# cpu_board_2.net
KiCad netlist of a schematic drawn in Altium Designer
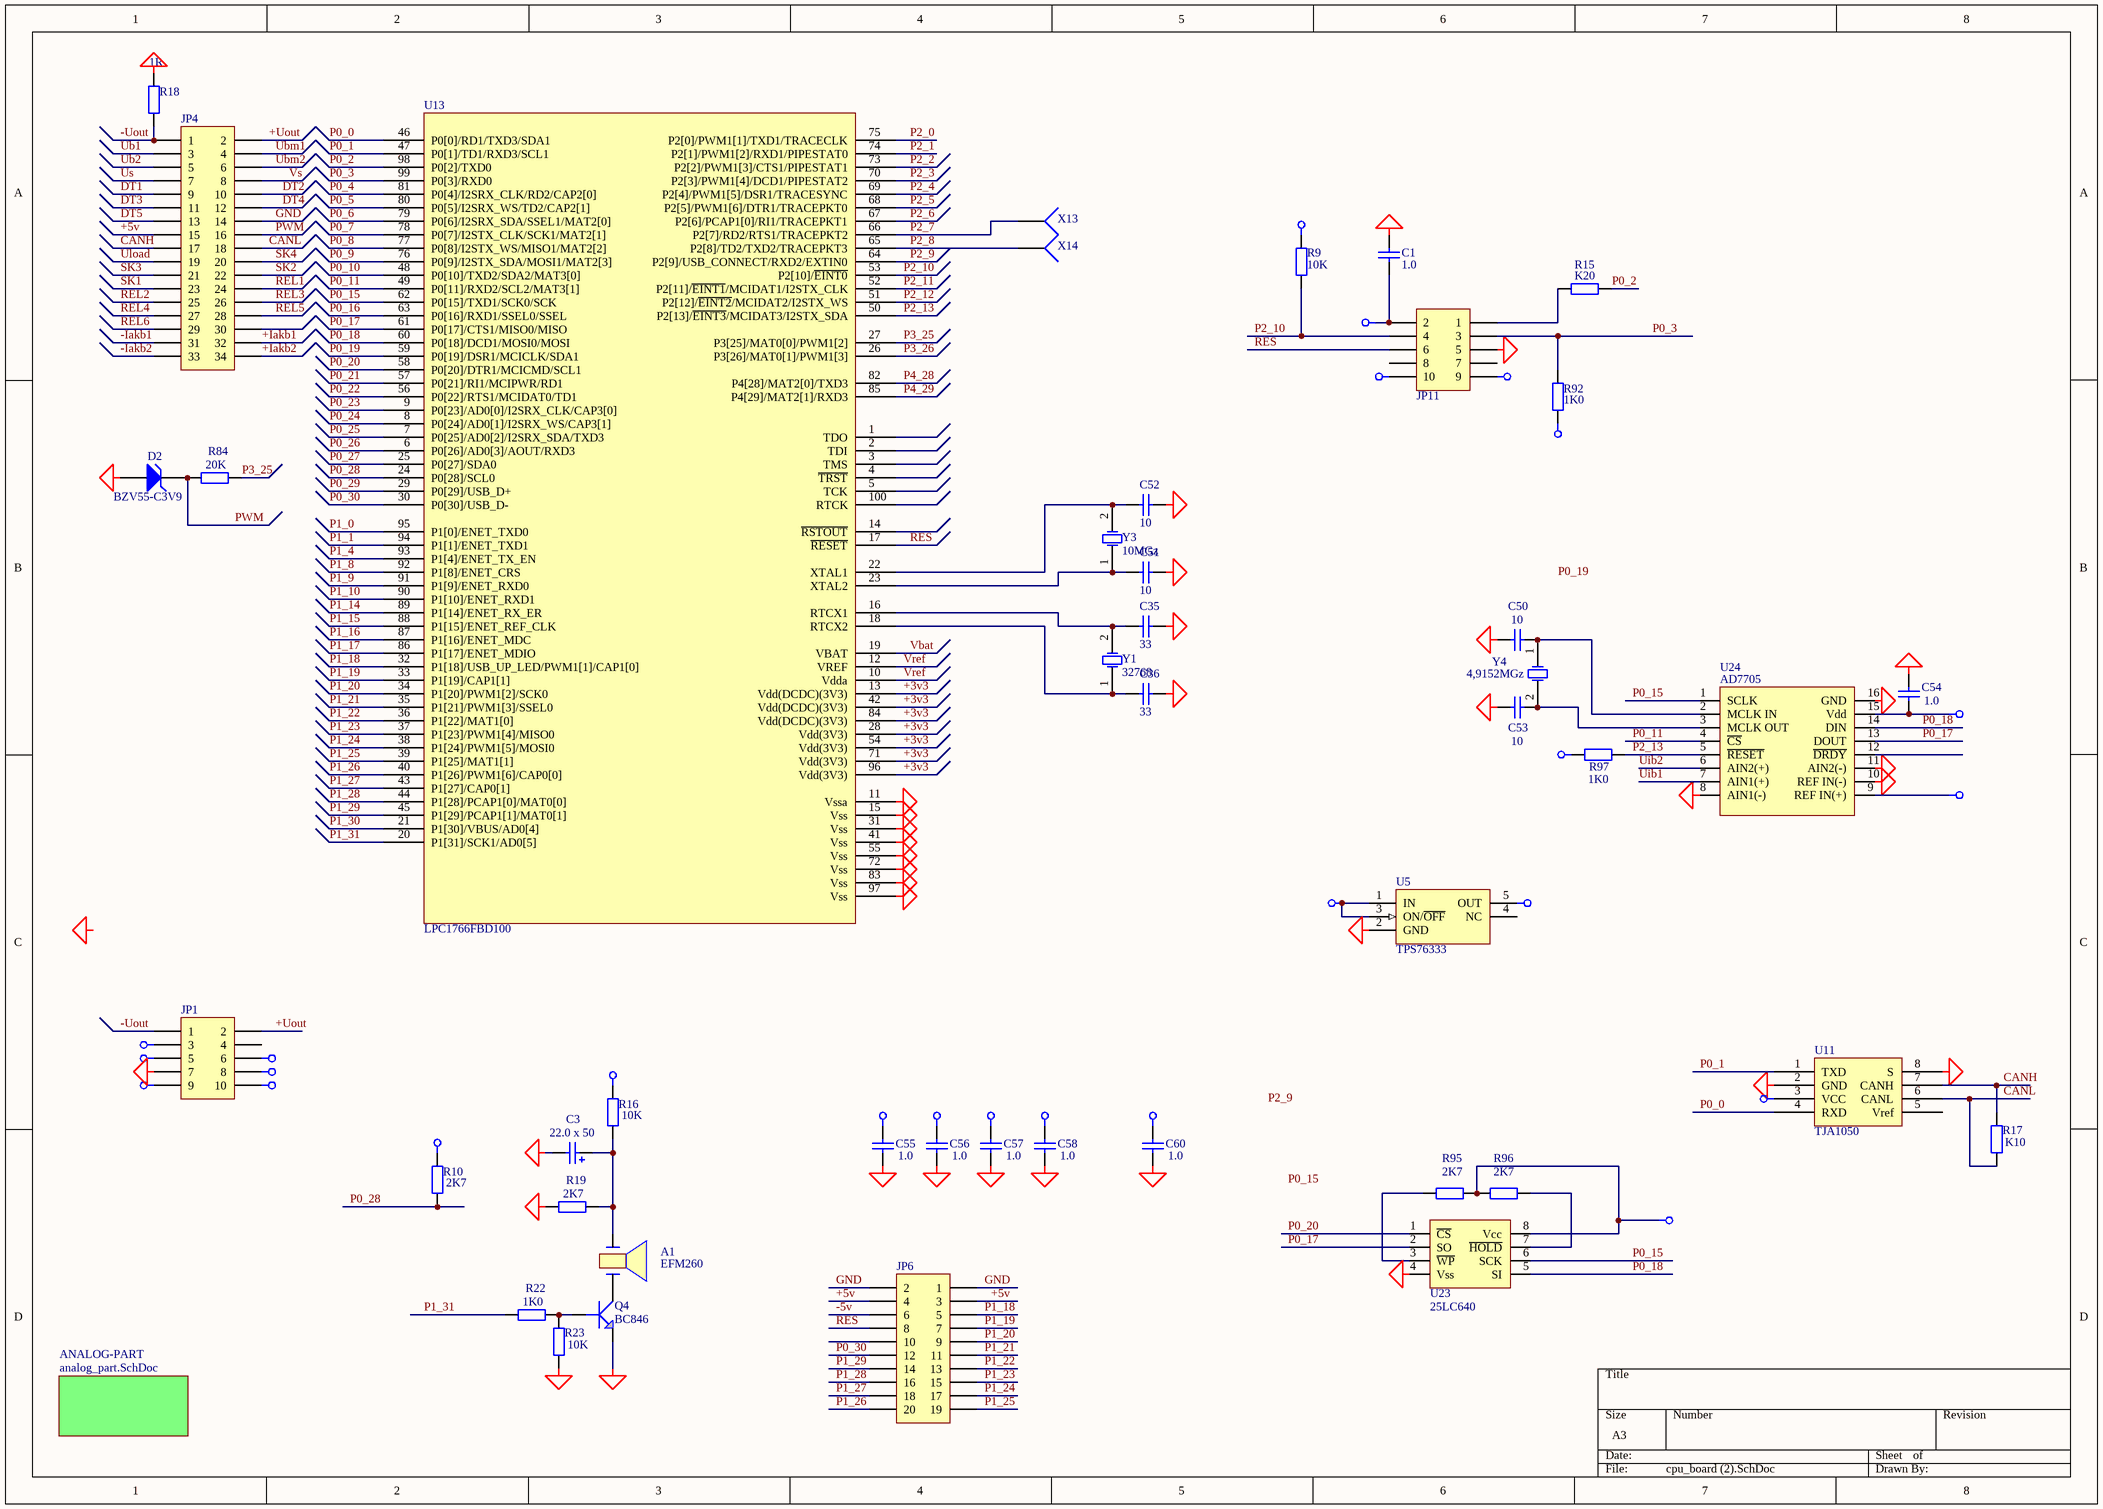
[diagram p0: cpu_board (2).SchDoc]

(export (version "E")
  (design (tool "Eeschema 10.0.6"))
  (components
    (comp (ref "A1")
      (value "EFM260")
      (footprint "Pjezo15")
      (description "Beeper")
      (libsource (lib "PAL") (part "PJEZ0"))
    )
    (comp (ref "C1")
      (value "1.0")
      (footprint "_1206")
      (description "Capacitor")
      (fields (field (name "MANUFACTURER") "Generic Components") (field (name "PUBLISHER") "Altium Limited"))
      (libsource (lib "Miscellaneous Devices") (part "Cap Semi"))
    )
    (comp (ref "C3")
      (value "22.0 x 50")
      (footprint "el3")
      (description "Polarized Capacitor (Radial)")
      (fields (field (name "MANUFACTURER") "Generic Components") (field (name "PUBLISHER") "Altium Limited"))
      (libsource (lib "PAL") (part "Cap Pol1"))
    )
    (comp (ref "C35")
      (value "33")
      (footprint "_1206")
      (description "Capacitor (Semiconductor SIM Model)")
      (fields (field (name "MANUFACTURER") "Generic Components") (field (name "PUBLISHER") "Altium Limited"))
      (libsource (lib "Miscellaneous Devices") (part "Cap Semi"))
    )
    (comp (ref "C36")
      (value "33")
      (footprint "_1206")
      (description "Capacitor (Semiconductor SIM Model)")
      (fields (field (name "MANUFACTURER") "Generic Components") (field (name "PUBLISHER") "Altium Limited"))
      (libsource (lib "Miscellaneous Devices") (part "Cap Semi"))
    )
    (comp (ref "C50")
      (value "10")
      (footprint "_1206")
      (description "Capacitor")
      (fields (field (name "MANUFACTURER") "Generic Components") (field (name "PUBLISHER") "Altium Limited"))
      (libsource (lib "") (part "Cap Semi_1"))
    )
    (comp (ref "C51")
      (value "10")
      (footprint "_1206")
      (description "Capacitor")
      (fields (field (name "MANUFACTURER") "Generic Components") (field (name "PUBLISHER") "Altium Limited"))
      (libsource (lib "Miscellaneous Devices") (part "Cap Semi"))
    )
    (comp (ref "C52")
      (value "10")
      (footprint "_1206")
      (description "Capacitor")
      (fields (field (name "MANUFACTURER") "Generic Components") (field (name "PUBLISHER") "Altium Limited"))
      (libsource (lib "Miscellaneous Devices") (part "Cap Semi"))
    )
    (comp (ref "C53")
      (value "10")
      (footprint "_1206")
      (description "Capacitor")
      (fields (field (name "MANUFACTURER") "Generic Components") (field (name "PUBLISHER") "Altium Limited"))
      (libsource (lib "") (part "Cap Semi_1"))
    )
    (comp (ref "C54")
      (value "1.0")
      (footprint "_1206")
      (description "Capacitor")
      (fields (field (name "MANUFACTURER") "Generic Components") (field (name "PUBLISHER") "Altium Limited"))
      (libsource (lib "Miscellaneous Devices") (part "Cap Semi"))
    )
    (comp (ref "C55")
      (value "1.0")
      (footprint "_1206")
      (description "Capacitor")
      (fields (field (name "MANUFACTURER") "Generic Components") (field (name "PUBLISHER") "Altium Limited"))
      (libsource (lib "Miscellaneous Devices") (part "Cap Semi"))
    )
    (comp (ref "C56")
      (value "1.0")
      (footprint "_1206")
      (description "Capacitor")
      (fields (field (name "MANUFACTURER") "Generic Components") (field (name "PUBLISHER") "Altium Limited"))
      (libsource (lib "Miscellaneous Devices") (part "Cap Semi"))
    )
    (comp (ref "C57")
      (value "1.0")
      (footprint "_1206")
      (description "Capacitor")
      (fields (field (name "MANUFACTURER") "Generic Components") (field (name "PUBLISHER") "Altium Limited"))
      (libsource (lib "Miscellaneous Devices") (part "Cap Semi"))
    )
    (comp (ref "C58")
      (value "1.0")
      (footprint "_1206")
      (description "Capacitor")
      (fields (field (name "MANUFACTURER") "Generic Components") (field (name "PUBLISHER") "Altium Limited"))
      (libsource (lib "Miscellaneous Devices") (part "Cap Semi"))
    )
    (comp (ref "C60")
      (value "1.0")
      (footprint "_1206")
      (description "Capacitor")
      (fields (field (name "MANUFACTURER") "Generic Components") (field (name "PUBLISHER") "Altium Limited"))
      (libsource (lib "Miscellaneous Devices") (part "Cap Semi"))
    )
    (comp (ref "D2")
      (value "BZV55-C3V9")
      (footprint "_1206d")
      (description "Zener Diode")
      (fields (field (name "MANUFACTURER") "Generic Components") (field (name "PUBLISHER") "Altium Limited"))
      (libsource (lib "Miscellaneous Devices") (part "D Zener"))
    )
    (comp (ref "JP1")
      (value "PBD-10")
      (footprint "HDR2X5")
      (description "Header, 5-Pin, Dual row")
      (fields (field (name "MANUFACTURER") "Generic Components") (field (name "PUBLISHER") "Altium Limited"))
      (libsource (lib "Miscellaneous Connectors") (part "Header 5X2"))
    )
    (comp (ref "JP4")
      (value "IDC34")
      (footprint "IDC34M")
      (description "Header, 17-Pin, Dual row")
      (fields (field (name "MANUFACTURER") "Generic Components") (field (name "PUBLISHER") "Altium Limited"))
      (libsource (lib "Miscellaneous Connectors") (part "Header 17X2"))
    )
    (comp (ref "JP6")
      (value "PBD-20")
      (footprint "HDR2X10")
      (description "Header, 10-Pin, Dual row")
      (fields (field (name "MANUFACTURER") "Generic Components") (field (name "PUBLISHER") "Altium Limited"))
      (libsource (lib "Miscellaneous Connectors") (part "Header 10X2"))
    )
    (comp (ref "JP11")
      (value "PLHD-10")
      (footprint "HDR2X5")
      (description "Header, 5-Pin, Dual row")
      (fields (field (name "MANUFACTURER") "Generic Components") (field (name "PUBLISHER") "Altium Limited"))
      (libsource (lib "") (part "Header 5X2_1"))
    )
    (comp (ref "Q4")
      (value "BC846")
      (footprint "SO-G3")
      (description "Bipolar transistor")
      (libsource (lib "MAIN") (part "GT122"))
    )
    (comp (ref "R9")
      (value "10K")
      (footprint "_1206")
      (description "Resistor")
      (fields (field (name "MANUFACTURER") "Generic Components") (field (name "PUBLISHER") "Altium Limited"))
      (libsource (lib "") (part "Res2_3"))
    )
    (comp (ref "R10")
      (value "2K7")
      (footprint "_1206")
      (description "Resistor")
      (fields (field (name "MANUFACTURER") "Generic Components") (field (name "PUBLISHER") "Altium Limited"))
      (libsource (lib "Miscellaneous Devices") (part "Res2"))
    )
    (comp (ref "R15")
      (value "K20")
      (footprint "_1206")
      (description "Resistor")
      (fields (field (name "MANUFACTURER") "Generic Components") (field (name "PUBLISHER") "Altium Limited"))
      (libsource (lib "") (part "Res2_2"))
    )
    (comp (ref "R16")
      (value "10K")
      (footprint "_1206")
      (description "Resistor")
      (fields (field (name "MANUFACTURER") "Generic Components") (field (name "PUBLISHER") "Altium Limited"))
      (libsource (lib "Miscellaneous Devices") (part "Res2"))
    )
    (comp (ref "R17")
      (value "K10")
      (footprint "_1206")
      (description "Resistor")
      (fields (field (name "MANUFACTURER") "Generic Components") (field (name "PUBLISHER") "Altium Limited"))
      (libsource (lib "Miscellaneous Devices") (part "Res2"))
    )
    (comp (ref "R18")
      (value "1R")
      (footprint "_1206")
      (description "Resistor")
      (fields (field (name "MANUFACTURER") "Generic Components") (field (name "PUBLISHER") "Altium Limited"))
      (libsource (lib "Miscellaneous Devices") (part "Res2"))
    )
    (comp (ref "R19")
      (value "2K7")
      (footprint "_1206")
      (description "Resistor")
      (fields (field (name "MANUFACTURER") "Generic Components") (field (name "PUBLISHER") "Altium Limited"))
      (libsource (lib "") (part "Res2_2"))
    )
    (comp (ref "R22")
      (value "1K0")
      (footprint "_1206")
      (description "Resistor")
      (fields (field (name "MANUFACTURER") "Generic Components") (field (name "PUBLISHER") "Altium Limited"))
      (libsource (lib "") (part "Res2_2"))
    )
    (comp (ref "R23")
      (value "10K")
      (footprint "_1206")
      (description "Resistor")
      (fields (field (name "MANUFACTURER") "Generic Components") (field (name "PUBLISHER") "Altium Limited"))
      (libsource (lib "Miscellaneous Devices") (part "Res2"))
    )
    (comp (ref "R84")
      (value "20K")
      (footprint "_1206")
      (description "Resistor")
      (fields (field (name "MANUFACTURER") "Generic Components") (field (name "PUBLISHER") "Altium Limited"))
      (libsource (lib "") (part "Res2_2"))
    )
    (comp (ref "R92")
      (value "1K0")
      (footprint "_1206")
      (description "Resistor")
      (fields (field (name "MANUFACTURER") "Generic Components") (field (name "PUBLISHER") "Altium Limited"))
      (libsource (lib "") (part "Res2_1"))
    )
    (comp (ref "R95")
      (value "2K7")
      (footprint "_1206")
      (description "Resistor")
      (fields (field (name "MANUFACTURER") "Generic Components") (field (name "PUBLISHER") "Altium Limited"))
      (libsource (lib "") (part "Res2_2"))
    )
    (comp (ref "R96")
      (value "2K7")
      (footprint "_1206")
      (description "Resistor")
      (fields (field (name "MANUFACTURER") "Generic Components") (field (name "PUBLISHER") "Altium Limited"))
      (libsource (lib "") (part "Res2_2"))
    )
    (comp (ref "R97")
      (value "1K0")
      (footprint "_1206")
      (description "Resistor")
      (fields (field (name "MANUFACTURER") "Generic Components") (field (name "PUBLISHER") "Altium Limited"))
      (libsource (lib "") (part "Res2_1"))
    )
    (comp (ref "U5")
      (value "TPS76333")
      (footprint "SO-G5/P.95")
      (description "Voltage Regulator")
      (fields
        (field (name "MANUFACTURER") "National Semiconductor")
        (field (name "PUBLISHER") "Altium Limited")
      )
      (libsource (lib "NSC Power Mgt Voltage Regulator") (part "LP2980AIM5-3.3"))
    )
    (comp (ref "U11") (value "TJA1050") (footprint "SO-G8/D5") (libsource (lib "PAL") (part "TJA1050")))
    (comp (ref "U13")
      (value "LPC1766FBD100")
      (footprint "LPC2368")
      (libsource (lib "PAL") (part "LPC2368FBD100"))
    )
    (comp (ref "U23")
      (value "25LC640")
      (footprint "SO-G8/D5")
      (description "Memory")
      (libsource (lib "PAL") (part "25LC640"))
    )
    (comp (ref "U24")
      (value "AD7705")
      (footprint "SO-G16/D10.4")
      (description "ADC")
      (libsource (lib "PAL") (part "AD7705"))
    )
    (comp (ref "X13")
      (value "~")
      (footprint "PIN1")
      (description "Socket")
      (fields (field (name "MANUFACTURER") "Generic Components") (field (name "PUBLISHER") "Altium Limited"))
      (libsource (lib "Miscellaneous Connectors") (part "Socket"))
    )
    (comp (ref "X14")
      (value "~")
      (footprint "PIN1")
      (description "Socket")
      (fields (field (name "MANUFACTURER") "Generic Components") (field (name "PUBLISHER") "Altium Limited"))
      (libsource (lib "Miscellaneous Connectors") (part "Socket"))
    )
    (comp (ref "Y1")
      (value "32768")
      (footprint "QWARZ2")
      (description "Crystal Oscillator")
      (fields (field (name "MANUFACTURER") "Generic Components") (field (name "PUBLISHER") "Altium Limited"))
      (libsource (lib "") (part "XTAL_1"))
    )
    (comp (ref "Y3")
      (value "10MGz")
      (footprint "QWARZ1")
      (description "Crystal Oscillator")
      (fields (field (name "MANUFACTURER") "Generic Components") (field (name "PUBLISHER") "Altium Limited"))
      (libsource (lib "") (part "XTAL_1"))
    )
    (comp (ref "Y4")
      (value "4,9152MGz")
      (footprint "QWARZ1")
      (description "Crystal Oscillator")
      (fields (field (name "MANUFACTURER") "Generic Components") (field (name "PUBLISHER") "Altium Limited"))
      (libsource (lib "Miscellaneous Devices") (part "XTAL"))
    )
  )
  (nets
    (net (code "1") (name "+3v3") (class "Default")
      (node (ref "C1") (pin "1") (pinfunction "1_1") (pintype "passive"))
      (node (ref "C58") (pin "2") (pinfunction "2_2") (pintype "passive"))
      (node (ref "JP1") (pin "3") (pinfunction "3_3") (pintype "passive"))
      (node (ref "JP11") (pin "2") (pinfunction "2_2") (pintype "passive"))
      (node (ref "R10") (pin "2") (pinfunction "2_2") (pintype "passive"))
      (node (ref "R9") (pin "1") (pinfunction "1_1") (pintype "passive"))
      (node (ref "R92") (pin "2") (pinfunction "2_2") (pintype "passive"))
      (node (ref "U13") (pin "13") (pinfunction "Vdd(DCDC)(3V3)_13") (pintype "passive"))
      (node (ref "U13") (pin "28") (pinfunction "Vdd(3V3)_28") (pintype "passive"))
      (node (ref "U13") (pin "42") (pinfunction "Vdd(DCDC)(3V3)_42") (pintype "passive"))
      (node (ref "U13") (pin "54") (pinfunction "Vdd(3V3)_54") (pintype "passive"))
      (node (ref "U13") (pin "71") (pinfunction "Vdd(3V3)_71") (pintype "passive"))
      (node (ref "U13") (pin "84") (pinfunction "Vdd(DCDC)(3V3)_84") (pintype "passive"))
      (node (ref "U13") (pin "96") (pinfunction "Vdd(3V3)_96") (pintype "passive"))
    )
    (net (code "2") (name "+5v") (class "Default")
      (node (ref "C54") (pin "2") (pinfunction "2_2") (pintype "passive"))
      (node (ref "C55") (pin "2") (pinfunction "2_2") (pintype "passive"))
      (node (ref "C57") (pin "2") (pinfunction "2_2") (pintype "passive"))
      (node (ref "C60") (pin "2") (pinfunction "2_2") (pintype "passive"))
      (node (ref "JP1") (pin "5") (pinfunction "5_5") (pintype "passive"))
      (node (ref "JP4") (pin "15") (pinfunction "15_15") (pintype "passive"))
      (node (ref "JP6") (pin "3") (pinfunction "3_3") (pintype "passive"))
      (node (ref "JP6") (pin "4") (pinfunction "4_4") (pintype "passive"))
      (node (ref "R95") (pin "2") (pinfunction "2_2") (pintype "passive"))
      (node (ref "R96") (pin "1") (pinfunction "1_1") (pintype "passive"))
      (node (ref "R97") (pin "2") (pinfunction "2_2") (pintype "passive"))
      (node (ref "U11") (pin "3") (pinfunction "VCC_3") (pintype "passive"))
      (node (ref "U23") (pin "8") (pinfunction "Vcc_8") (pintype "passive"))
      (node (ref "U24") (pin "15") (pinfunction "Vdd_15") (pintype "passive"))
      (node (ref "U5") (pin "1") (pinfunction "IN_1") (pintype "power_in"))
      (node (ref "U5") (pin "3") (pinfunction "ON/~{OFF}_3") (pintype "input"))
    )
    (net (code "3") (name "+5v_iz") (class "Default")
      (node (ref "JP1") (pin "10") (pinfunction "10_10") (pintype "passive"))
      (node (ref "JP11") (pin "9") (pinfunction "9_9") (pintype "passive"))
    )
    (net (code "4") (name "+Uout") (class "Default")
      (node (ref "JP1") (pin "2") (pinfunction "2_2") (pintype "passive"))
      (node (ref "JP4") (pin "2") (pinfunction "2_2") (pintype "passive"))
      (node (ref "R16") (pin "2") (pinfunction "2_2") (pintype "passive"))
    )
    (net (code "5") (name "-5v") (class "Default")
      (node (ref "C56") (pin "2") (pinfunction "2_2") (pintype "passive"))
      (node (ref "JP1") (pin "8") (pinfunction "8_8") (pintype "passive"))
      (node (ref "JP6") (pin "6") (pinfunction "6_6") (pintype "passive"))
    )
    (net (code "6") (name "-5v_iz") (class "Default")
      (node (ref "JP1") (pin "9") (pinfunction "9_9") (pintype "passive"))
      (node (ref "JP11") (pin "10") (pinfunction "10_10") (pintype "passive"))
    )
    (net (code "7") (name "/+Iakb1") (class "Default")
      (node (ref "JP4") (pin "32") (pinfunction "32_32") (pintype "passive"))
    )
    (net (code "8") (name "/+Iakb2") (class "Default")
      (node (ref "JP4") (pin "34") (pinfunction "34_34") (pintype "passive"))
    )
    (net (code "9") (name "/-Iakb1") (class "Default")
      (node (ref "JP4") (pin "31") (pinfunction "31_31") (pintype "passive"))
    )
    (net (code "10") (name "/-Iakb2") (class "Default")
      (node (ref "JP4") (pin "33") (pinfunction "33_33") (pintype "passive"))
    )
    (net (code "11") (name "/-Uout") (class "Default")
      (node (ref "JP1") (pin "1") (pinfunction "1_1") (pintype "passive"))
      (node (ref "JP4") (pin "1") (pinfunction "1_1") (pintype "passive"))
      (node (ref "R18") (pin "1") (pinfunction "1_1") (pintype "passive"))
    )
    (net (code "12") (name "/CANH") (class "Default")
      (node (ref "JP4") (pin "17") (pinfunction "17_17") (pintype "passive"))
      (node (ref "R17") (pin "2") (pinfunction "2_2") (pintype "passive"))
      (node (ref "U11") (pin "7") (pinfunction "CANH_7") (pintype "passive"))
    )
    (net (code "13") (name "/CANL") (class "Default")
      (node (ref "JP4") (pin "18") (pinfunction "18_18") (pintype "passive"))
      (node (ref "R17") (pin "1") (pinfunction "1_1") (pintype "passive"))
      (node (ref "U11") (pin "6") (pinfunction "CANL_6") (pintype "passive"))
    )
    (net (code "14") (name "/DT1") (class "Default")
      (node (ref "JP4") (pin "9") (pinfunction "9_9") (pintype "passive"))
    )
    (net (code "15") (name "/DT2") (class "Default")
      (node (ref "JP4") (pin "10") (pinfunction "10_10") (pintype "passive"))
    )
    (net (code "16") (name "/DT3") (class "Default")
      (node (ref "JP4") (pin "11") (pinfunction "11_11") (pintype "passive"))
    )
    (net (code "17") (name "/DT4") (class "Default")
      (node (ref "JP4") (pin "12") (pinfunction "12_12") (pintype "passive"))
    )
    (net (code "18") (name "/DT5") (class "Default")
      (node (ref "JP4") (pin "13") (pinfunction "13_13") (pintype "passive"))
    )
    (net (code "19") (name "/P0_0") (class "Default")
      (node (ref "U11") (pin "4") (pinfunction "RXD_4") (pintype "passive"))
      (node (ref "U13") (pin "46") (pinfunction "P0[0]/RD1/TXD3/SDA1_46") (pintype "passive"))
    )
    (net (code "20") (name "/P0_1") (class "Default")
      (node (ref "U11") (pin "1") (pinfunction "TXD_1") (pintype "passive"))
      (node (ref "U13") (pin "47") (pinfunction "P0[1]/TD1/RXD3/SCL1_47") (pintype "passive"))
    )
    (net (code "21") (name "/P0_2") (class "Default")
      (node (ref "R15") (pin "2") (pinfunction "2_2") (pintype "passive"))
      (node (ref "U13") (pin "98") (pinfunction "P0[2]/TXD0_98") (pintype "passive"))
    )
    (net (code "22") (name "/P0_3") (class "Default")
      (node (ref "JP11") (pin "3") (pinfunction "3_3") (pintype "passive"))
      (node (ref "R92") (pin "1") (pinfunction "1_1") (pintype "passive"))
      (node (ref "U13") (pin "99") (pinfunction "P0[3]/RXD0_99") (pintype "passive"))
    )
    (net (code "23") (name "/P0_4") (class "Default")
      (node (ref "U13") (pin "81") (pinfunction "P0[4]/I2SRX_CLK/RD2/CAP2[0]_81") (pintype "passive"))
    )
    (net (code "24") (name "/P0_5") (class "Default")
      (node (ref "U13") (pin "80") (pinfunction "P0[5]/I2SRX_WS/TD2/CAP2[1]_80") (pintype "passive"))
    )
    (net (code "25") (name "/P0_6") (class "Default")
      (node (ref "U13") (pin "79") (pinfunction "P0[6]/I2SRX_SDA/SSEL1/MAT2[0]_79") (pintype "passive"))
    )
    (net (code "26") (name "/P0_7") (class "Default")
      (node (ref "U13") (pin "78") (pinfunction "P0[7]/I2STX_CLK/SCK1/MAT2[1]_78") (pintype "passive"))
    )
    (net (code "27") (name "/P0_8") (class "Default")
      (node (ref "U13") (pin "77") (pinfunction "P0[8]/I2STX_WS/MISO1/MAT2[2]_77") (pintype "passive"))
    )
    (net (code "28") (name "/P0_9") (class "Default")
      (node (ref "U13") (pin "76") (pinfunction "P0[9]/I2STX_SDA/MOSI1/MAT2[3]_76") (pintype "passive"))
    )
    (net (code "29") (name "/P0_10") (class "Default")
      (node (ref "U13") (pin "48") (pinfunction "P0[10]/TXD2/SDA2/MAT3[0]_48") (pintype "passive"))
    )
    (net (code "30") (name "/P0_11") (class "Default")
      (node (ref "U13") (pin "49") (pinfunction "P0[11]/RXD2/SCL2/MAT3[1]_49") (pintype "passive"))
      (node (ref "U24") (pin "4") (pinfunction "~{CS}_4") (pintype "passive"))
    )
    (net (code "31") (name "/P0_15") (class "Default")
      (node (ref "U13") (pin "62") (pinfunction "P0[15]/TXD1/SCK0/SCK_62") (pintype "passive"))
      (node (ref "U23") (pin "6") (pinfunction "SCK_6") (pintype "passive"))
      (node (ref "U24") (pin "1") (pinfunction "SCLK_1") (pintype "passive"))
    )
    (net (code "32") (name "/P0_16") (class "Default")
      (node (ref "U13") (pin "63") (pinfunction "P0[16]/RXD1/SSEL0/SSEL_63") (pintype "passive"))
    )
    (net (code "33") (name "/P0_17") (class "Default")
      (node (ref "U13") (pin "61") (pinfunction "P0[17]/CTS1/MISO0/MISO_61") (pintype "passive"))
      (node (ref "U23") (pin "2") (pinfunction "SO_2") (pintype "passive"))
      (node (ref "U24") (pin "13") (pinfunction "DOUT_13") (pintype "passive"))
    )
    (net (code "34") (name "/P0_18") (class "Default")
      (node (ref "U13") (pin "60") (pinfunction "P0[18]/DCD1/MOSI0/MOSI_60") (pintype "passive"))
      (node (ref "U23") (pin "5") (pinfunction "SI_5") (pintype "passive"))
      (node (ref "U24") (pin "14") (pinfunction "DIN_14") (pintype "passive"))
    )
    (net (code "35") (name "/P0_19") (class "Default")
      (node (ref "U13") (pin "59") (pinfunction "P0[19]/DSR1/MCICLK/SDA1_59") (pintype "passive"))
    )
    (net (code "36") (name "/P0_20") (class "Default")
      (node (ref "U13") (pin "58") (pinfunction "P0[20]/DTR1/MCICMD/SCL1_58") (pintype "passive"))
      (node (ref "U23") (pin "1") (pinfunction "~{CS}_1") (pintype "passive"))
    )
    (net (code "37") (name "/P0_21") (class "Default")
      (node (ref "U13") (pin "57") (pinfunction "P0[21]/RI1/MCIPWR/RD1_57") (pintype "passive"))
    )
    (net (code "38") (name "/P0_22") (class "Default")
      (node (ref "U13") (pin "56") (pinfunction "P0[22]/RTS1/MCIDAT0/TD1_56") (pintype "passive"))
    )
    (net (code "39") (name "/P0_23") (class "Default")
      (node (ref "U13") (pin "9") (pinfunction "P0[23]/AD0[0]/I2SRX_CLK/CAP3[0]_9") (pintype "passive"))
    )
    (net (code "40") (name "/P0_24") (class "Default")
      (node (ref "U13") (pin "8") (pinfunction "P0[24]/AD0[1]/I2SRX_WS/CAP3[1]_8") (pintype "passive"))
    )
    (net (code "41") (name "/P0_25") (class "Default")
      (node (ref "U13") (pin "7") (pinfunction "P0[25]/AD0[2]/I2SRX_SDA/TXD3_7") (pintype "passive"))
    )
    (net (code "42") (name "/P0_26") (class "Default")
      (node (ref "U13") (pin "6") (pinfunction "P0[26]/AD0[3]/AOUT/RXD3_6") (pintype "passive"))
    )
    (net (code "43") (name "/P0_27") (class "Default")
      (node (ref "U13") (pin "25") (pinfunction "P0[27]/SDA0_25") (pintype "passive"))
    )
    (net (code "44") (name "/P0_28") (class "Default")
      (node (ref "R10") (pin "1") (pinfunction "1_1") (pintype "passive"))
      (node (ref "U13") (pin "24") (pinfunction "P0[28]/SCL0_24") (pintype "passive"))
    )
    (net (code "45") (name "/P0_29") (class "Default")
      (node (ref "U13") (pin "29") (pinfunction "P0[29]/USB_D+_29") (pintype "passive"))
    )
    (net (code "46") (name "/P0_30") (class "Default")
      (node (ref "JP6") (pin "12") (pinfunction "12_12") (pintype "passive"))
      (node (ref "U13") (pin "30") (pinfunction "P0[30]/USB_D-_30") (pintype "passive"))
    )
    (net (code "47") (name "/P1_0") (class "Default")
      (node (ref "U13") (pin "95") (pinfunction "P1[0]/ENET_TXD0_95") (pintype "passive"))
    )
    (net (code "48") (name "/P1_1") (class "Default")
      (node (ref "U13") (pin "94") (pinfunction "P1[1]/ENET_TXD1_94") (pintype "passive"))
    )
    (net (code "49") (name "/P1_4") (class "Default")
      (node (ref "U13") (pin "93") (pinfunction "P1[4]/ENET_TX_EN_93") (pintype "passive"))
    )
    (net (code "50") (name "/P1_8") (class "Default")
      (node (ref "U13") (pin "92") (pinfunction "P1[8]/ENET_CRS_92") (pintype "passive"))
    )
    (net (code "51") (name "/P1_9") (class "Default")
      (node (ref "U13") (pin "91") (pinfunction "P1[9]/ENET_RXD0_91") (pintype "passive"))
    )
    (net (code "52") (name "/P1_10") (class "Default")
      (node (ref "U13") (pin "90") (pinfunction "P1[10]/ENET_RXD1_90") (pintype "passive"))
    )
    (net (code "53") (name "/P1_14") (class "Default")
      (node (ref "U13") (pin "89") (pinfunction "P1[14]/ENET_RX_ER_89") (pintype "passive"))
    )
    (net (code "54") (name "/P1_15") (class "Default")
      (node (ref "U13") (pin "88") (pinfunction "P1[15]/ENET_REF_CLK_88") (pintype "passive"))
    )
    (net (code "55") (name "/P1_16") (class "Default")
      (node (ref "U13") (pin "87") (pinfunction "P1[16]/ENET_MDC_87") (pintype "passive"))
    )
    (net (code "56") (name "/P1_17") (class "Default")
      (node (ref "U13") (pin "86") (pinfunction "P1[17]/ENET_MDIO_86") (pintype "passive"))
    )
    (net (code "57") (name "/P1_18") (class "Default")
      (node (ref "JP6") (pin "5") (pinfunction "5_5") (pintype "passive"))
      (node (ref "U13") (pin "32") (pinfunction "P1[18]/USB_UP_LED/PWM1[1]/CAP1[0]_32") (pintype "passive"))
    )
    (net (code "58") (name "/P1_19") (class "Default")
      (node (ref "JP6") (pin "7") (pinfunction "7_7") (pintype "passive"))
      (node (ref "U13") (pin "33") (pinfunction "P1[19]/CAP1[1]_33") (pintype "passive"))
    )
    (net (code "59") (name "/P1_20") (class "Default")
      (node (ref "JP6") (pin "9") (pinfunction "9_9") (pintype "passive"))
      (node (ref "U13") (pin "34") (pinfunction "P1[20]/PWM1[2]/SCK0_34") (pintype "passive"))
    )
    (net (code "60") (name "/P1_21") (class "Default")
      (node (ref "JP6") (pin "11") (pinfunction "11_11") (pintype "passive"))
      (node (ref "U13") (pin "35") (pinfunction "P1[21]/PWM1[3]/SSEL0_35") (pintype "passive"))
    )
    (net (code "61") (name "/P1_22") (class "Default")
      (node (ref "JP6") (pin "13") (pinfunction "13_13") (pintype "passive"))
      (node (ref "U13") (pin "36") (pinfunction "P1[22]/MAT1[0]_36") (pintype "passive"))
    )
    (net (code "62") (name "/P1_23") (class "Default")
      (node (ref "JP6") (pin "15") (pinfunction "15_15") (pintype "passive"))
      (node (ref "U13") (pin "37") (pinfunction "P1[23]/PWM1[4]/MISO0_37") (pintype "passive"))
    )
    (net (code "63") (name "/P1_24") (class "Default")
      (node (ref "JP6") (pin "17") (pinfunction "17_17") (pintype "passive"))
      (node (ref "U13") (pin "38") (pinfunction "P1[24]/PWM1[5]/MOSI0_38") (pintype "passive"))
    )
    (net (code "64") (name "/P1_25") (class "Default")
      (node (ref "JP6") (pin "19") (pinfunction "19_19") (pintype "passive"))
      (node (ref "U13") (pin "39") (pinfunction "P1[25]/MAT1[1]_39") (pintype "passive"))
    )
    (net (code "65") (name "/P1_26") (class "Default")
      (node (ref "JP6") (pin "20") (pinfunction "20_20") (pintype "passive"))
      (node (ref "U13") (pin "40") (pinfunction "P1[26]/PWM1[6]/CAP0[0]_40") (pintype "passive"))
    )
    (net (code "66") (name "/P1_27") (class "Default")
      (node (ref "JP6") (pin "18") (pinfunction "18_18") (pintype "passive"))
      (node (ref "U13") (pin "43") (pinfunction "P1[27]/CAP0[1]_43") (pintype "passive"))
    )
    (net (code "67") (name "/P1_28") (class "Default")
      (node (ref "JP6") (pin "16") (pinfunction "16_16") (pintype "passive"))
      (node (ref "U13") (pin "44") (pinfunction "P1[28]/PCAP1[0]/MAT0[0]_44") (pintype "passive"))
    )
    (net (code "68") (name "/P1_29") (class "Default")
      (node (ref "JP6") (pin "14") (pinfunction "14_14") (pintype "passive"))
      (node (ref "U13") (pin "45") (pinfunction "P1[29]/PCAP1[1]/MAT0[1]_45") (pintype "passive"))
    )
    (net (code "69") (name "/P1_30") (class "Default")
      (node (ref "U13") (pin "21") (pinfunction "P1[30]/VBUS/AD0[4]_21") (pintype "passive"))
    )
    (net (code "70") (name "/P1_31") (class "Default")
      (node (ref "R22") (pin "1") (pinfunction "1_1") (pintype "passive"))
      (node (ref "U13") (pin "20") (pinfunction "P1[31]/SCK1/AD0[5]_20") (pintype "passive"))
    )
    (net (code "71") (name "/P2_0") (class "Default")
      (node (ref "U13") (pin "75") (pinfunction "P2[0]/PWM1[1]/TXD1/TRACECLK_75") (pintype "passive"))
    )
    (net (code "72") (name "/P2_1") (class "Default")
      (node (ref "U13") (pin "74") (pinfunction "P2[1]/PWM1[2]/RXD1/PIPESTAT0_74") (pintype "passive"))
    )
    (net (code "73") (name "/P2_2") (class "Default")
      (node (ref "U13") (pin "73") (pinfunction "P2[2]/PWM1[3]/CTS1/PIPESTAT1_73") (pintype "passive"))
    )
    (net (code "74") (name "/P2_3") (class "Default")
      (node (ref "U13") (pin "70") (pinfunction "P2[3]/PWM1[4]/DCD1/PIPESTAT2_70") (pintype "passive"))
    )
    (net (code "75") (name "/P2_4") (class "Default")
      (node (ref "U13") (pin "69") (pinfunction "P2[4]/PWM1[5]/DSR1/TRACESYNC_69") (pintype "passive"))
    )
    (net (code "76") (name "/P2_5") (class "Default")
      (node (ref "U13") (pin "68") (pinfunction "P2[5]/PWM1[6]/DTR1/TRACEPKT0_68") (pintype "passive"))
    )
    (net (code "77") (name "/P2_6") (class "Default")
      (node (ref "U13") (pin "67") (pinfunction "P2[6]/PCAP1[0]/RI1/TRACEPKT1_67") (pintype "passive"))
    )
    (net (code "78") (name "/P2_7") (class "Default")
      (node (ref "U13") (pin "66") (pinfunction "P2[7]/RD2/RTS1/TRACEPKT2_66") (pintype "passive"))
      (node (ref "X13") (pin "1") (pinfunction "1_1") (pintype "passive"))
    )
    (net (code "79") (name "/P2_8") (class "Default")
      (node (ref "U13") (pin "65") (pinfunction "P2[8]/TD2/TXD2/TRACEPKT3_65") (pintype "passive"))
      (node (ref "X14") (pin "1") (pinfunction "1_1") (pintype "passive"))
    )
    (net (code "80") (name "/P2_9") (class "Default")
      (node (ref "U13") (pin "64") (pinfunction "P2[9]/USB_CONNECT/RXD2/EXTIN0_64") (pintype "passive"))
    )
    (net (code "81") (name "/P2_10") (class "Default")
      (node (ref "JP11") (pin "4") (pinfunction "4_4") (pintype "passive"))
      (node (ref "R9") (pin "2") (pinfunction "2_2") (pintype "passive"))
      (node (ref "U13") (pin "53") (pinfunction "P2[10]/~{EINT0}_53") (pintype "passive"))
    )
    (net (code "82") (name "/P2_11") (class "Default")
      (node (ref "U13") (pin "52") (pinfunction "P2[11]/~{EINT1}/MCIDAT1/I2STX_CLK_52") (pintype "passive"))
    )
    (net (code "83") (name "/P2_12") (class "Default")
      (node (ref "U13") (pin "51") (pinfunction "P2[12]/~{EINT2}/MCIDAT2/I2STX_WS_51") (pintype "passive"))
    )
    (net (code "84") (name "/P2_13") (class "Default")
      (node (ref "R97") (pin "1") (pinfunction "1_1") (pintype "passive"))
      (node (ref "U13") (pin "50") (pinfunction "P2[13]/~{EINT3}/MCIDAT3/I2STX_SDA_50") (pintype "passive"))
      (node (ref "U24") (pin "5") (pinfunction "~{RESET}_5") (pintype "passive"))
    )
    (net (code "85") (name "/P3_25") (class "Default")
      (node (ref "R84") (pin "2") (pinfunction "2_2") (pintype "passive"))
      (node (ref "U13") (pin "27") (pinfunction "P3[25]/MAT0[0]/PWM1[2]_27") (pintype "passive"))
    )
    (net (code "86") (name "/P3_26") (class "Default")
      (node (ref "U13") (pin "26") (pinfunction "P3[26]/MAT0[1]/PWM1[3]_26") (pintype "passive"))
    )
    (net (code "87") (name "/P4_28") (class "Default")
      (node (ref "U13") (pin "82") (pinfunction "P4[28]/MAT2[0]/TXD3_82") (pintype "passive"))
    )
    (net (code "88") (name "/P4_29") (class "Default")
      (node (ref "U13") (pin "85") (pinfunction "P4[29]/MAT2[1]/RXD3_85") (pintype "passive"))
    )
    (net (code "89") (name "/PWM") (class "Default")
      (node (ref "D2") (pin "2") (pinfunction "K_2") (pintype "passive"))
      (node (ref "JP4") (pin "16") (pinfunction "16_16") (pintype "passive"))
      (node (ref "R84") (pin "1") (pinfunction "1_1") (pintype "passive"))
    )
    (net (code "90") (name "/REL1") (class "Default")
      (node (ref "JP4") (pin "24") (pinfunction "24_24") (pintype "passive"))
    )
    (net (code "91") (name "/REL2") (class "Default")
      (node (ref "JP4") (pin "25") (pinfunction "25_25") (pintype "passive"))
    )
    (net (code "92") (name "/REL3") (class "Default")
      (node (ref "JP4") (pin "26") (pinfunction "26_26") (pintype "passive"))
    )
    (net (code "93") (name "/REL4") (class "Default")
      (node (ref "JP4") (pin "27") (pinfunction "27_27") (pintype "passive"))
    )
    (net (code "94") (name "/REL5") (class "Default")
      (node (ref "JP4") (pin "28") (pinfunction "28_28") (pintype "passive"))
    )
    (net (code "95") (name "/REL6") (class "Default")
      (node (ref "JP4") (pin "29") (pinfunction "29_29") (pintype "passive"))
    )
    (net (code "96") (name "/RES") (class "Default")
      (node (ref "JP11") (pin "6") (pinfunction "6_6") (pintype "passive"))
      (node (ref "JP6") (pin "8") (pinfunction "8_8") (pintype "passive"))
      (node (ref "U13") (pin "17") (pinfunction "~{RESET}_17") (pintype "passive"))
    )
    (net (code "97") (name "/SK1") (class "Default")
      (node (ref "JP4") (pin "23") (pinfunction "23_23") (pintype "passive"))
    )
    (net (code "98") (name "/SK2") (class "Default")
      (node (ref "JP4") (pin "22") (pinfunction "22_22") (pintype "passive"))
    )
    (net (code "99") (name "/SK3") (class "Default")
      (node (ref "JP4") (pin "21") (pinfunction "21_21") (pintype "passive"))
    )
    (net (code "100") (name "/SK4") (class "Default")
      (node (ref "JP4") (pin "20") (pinfunction "20_20") (pintype "passive"))
    )
    (net (code "101") (name "/Ub1") (class "Default")
      (node (ref "JP4") (pin "3") (pinfunction "3_3") (pintype "passive"))
    )
    (net (code "102") (name "/Ub2") (class "Default")
      (node (ref "JP4") (pin "5") (pinfunction "5_5") (pintype "passive"))
    )
    (net (code "103") (name "/Ubm1") (class "Default")
      (node (ref "JP4") (pin "4") (pinfunction "4_4") (pintype "passive"))
    )
    (net (code "104") (name "/Ubm2") (class "Default")
      (node (ref "JP4") (pin "6") (pinfunction "6_6") (pintype "passive"))
    )
    (net (code "105") (name "/Uib1") (class "Default")
      (node (ref "U24") (pin "7") (pinfunction "AIN1(+)_7") (pintype "passive"))
    )
    (net (code "106") (name "/Uib2") (class "Default")
      (node (ref "U24") (pin "6") (pinfunction "AIN2(+)_6") (pintype "passive"))
    )
    (net (code "107") (name "/Uload") (class "Default")
      (node (ref "JP4") (pin "19") (pinfunction "19_19") (pintype "passive"))
    )
    (net (code "108") (name "/Us") (class "Default")
      (node (ref "JP4") (pin "7") (pinfunction "7_7") (pintype "passive"))
    )
    (net (code "109") (name "/Vs") (class "Default")
      (node (ref "JP4") (pin "8") (pinfunction "8_8") (pintype "passive"))
    )
    (net (code "110") (name "GND") (class "Default")
      (node (ref "C1") (pin "2") (pinfunction "2_2") (pintype "passive"))
      (node (ref "C3") (pin "2") (pinfunction "2_2") (pintype "passive"))
      (node (ref "C35") (pin "1") (pinfunction "1_1") (pintype "passive"))
      (node (ref "C36") (pin "1") (pinfunction "1_1") (pintype "passive"))
      (node (ref "C50") (pin "1") (pinfunction "1_1") (pintype "passive"))
      (node (ref "C51") (pin "1") (pinfunction "1_1") (pintype "passive"))
      (node (ref "C52") (pin "1") (pinfunction "1_1") (pintype "passive"))
      (node (ref "C53") (pin "1") (pinfunction "1_1") (pintype "passive"))
      (node (ref "C54") (pin "1") (pinfunction "1_1") (pintype "passive"))
      (node (ref "C55") (pin "1") (pinfunction "1_1") (pintype "passive"))
      (node (ref "C56") (pin "1") (pinfunction "1_1") (pintype "passive"))
      (node (ref "C57") (pin "1") (pinfunction "1_1") (pintype "passive"))
      (node (ref "C58") (pin "1") (pinfunction "1_1") (pintype "passive"))
      (node (ref "C60") (pin "1") (pinfunction "1_1") (pintype "passive"))
      (node (ref "D2") (pin "1") (pinfunction "A_1") (pintype "passive"))
      (node (ref "JP1") (pin "7") (pinfunction "7_7") (pintype "passive"))
      (node (ref "JP11") (pin "5") (pinfunction "5_5") (pintype "passive"))
      (node (ref "JP4") (pin "14") (pinfunction "14_14") (pintype "passive"))
      (node (ref "JP6") (pin "1") (pinfunction "1_1") (pintype "passive"))
      (node (ref "JP6") (pin "2") (pinfunction "2_2") (pintype "passive"))
      (node (ref "Q4") (pin "2") (pinfunction "E_2") (pintype "passive"))
      (node (ref "R18") (pin "2") (pinfunction "2_2") (pintype "passive"))
      (node (ref "R19") (pin "1") (pinfunction "1_1") (pintype "passive"))
      (node (ref "R23") (pin "1") (pinfunction "1_1") (pintype "passive"))
      (node (ref "U11") (pin "2") (pinfunction "GND_2") (pintype "passive"))
      (node (ref "U11") (pin "8") (pinfunction "S_8") (pintype "passive"))
      (node (ref "U13") (pin "11") (pinfunction "Vssa_11") (pintype "passive"))
      (node (ref "U13") (pin "15") (pinfunction "Vss_15") (pintype "passive"))
      (node (ref "U13") (pin "31") (pinfunction "Vss_31") (pintype "passive"))
      (node (ref "U13") (pin "41") (pinfunction "Vss_41") (pintype "passive"))
      (node (ref "U13") (pin "55") (pinfunction "Vss_55") (pintype "passive"))
      (node (ref "U13") (pin "72") (pinfunction "Vss_72") (pintype "passive"))
      (node (ref "U13") (pin "83") (pinfunction "Vss_83") (pintype "passive"))
      (node (ref "U13") (pin "97") (pinfunction "Vss_97") (pintype "passive"))
      (node (ref "U23") (pin "4") (pinfunction "Vss_4") (pintype "passive"))
      (node (ref "U24") (pin "10") (pinfunction "REF_IN(-)_10") (pintype "passive"))
      (node (ref "U24") (pin "11") (pinfunction "AIN2(-)_11") (pintype "passive"))
      (node (ref "U24") (pin "16") (pinfunction "GND_16") (pintype "passive"))
      (node (ref "U24") (pin "8") (pinfunction "AIN1(-)_8") (pintype "passive"))
      (node (ref "U5") (pin "2") (pinfunction "GND_2") (pintype "power_in"))
    )
    (net (code "111") (name "Net-(A1-Pad2)") (class "Default")
      (node (ref "A1") (pin "2") (pinfunction "2_2") (pintype "passive"))
      (node (ref "C3") (pin "1") (pinfunction "1_1") (pintype "passive"))
      (node (ref "R16") (pin "1") (pinfunction "1_1") (pintype "passive"))
      (node (ref "R19") (pin "2") (pinfunction "2_2") (pintype "passive"))
    )
    (net (code "112") (name "Net-(JP11-Pad1)") (class "Default")
      (node (ref "JP11") (pin "1") (pinfunction "1_1") (pintype "passive"))
      (node (ref "R15") (pin "1") (pinfunction "1_1") (pintype "passive"))
    )
    (net (code "113") (name "Net-(Q4-B)") (class "Default")
      (node (ref "Q4") (pin "1") (pinfunction "B_1") (pintype "passive"))
      (node (ref "R22") (pin "2") (pinfunction "2_2") (pintype "passive"))
      (node (ref "R23") (pin "2") (pinfunction "2_2") (pintype "passive"))
    )
    (net (code "114") (name "Net-(Q4-C)") (class "Default")
      (node (ref "A1") (pin "1") (pinfunction "1_1") (pintype "passive"))
      (node (ref "Q4") (pin "3") (pinfunction "C_3") (pintype "passive"))
    )
    (net (code "115") (name "Net-(U13-RTCX1)") (class "Default")
      (node (ref "C35") (pin "2") (pinfunction "2_2") (pintype "passive"))
      (node (ref "U13") (pin "16") (pinfunction "RTCX1_16") (pintype "passive"))
      (node (ref "Y1") (pin "2") (pinfunction "OSC2_2") (pintype "passive"))
    )
    (net (code "116") (name "Net-(U13-RTCX2)") (class "Default")
      (node (ref "C36") (pin "2") (pinfunction "2_2") (pintype "passive"))
      (node (ref "U13") (pin "18") (pinfunction "RTCX2_18") (pintype "passive"))
      (node (ref "Y1") (pin "1") (pinfunction "OSC1_1") (pintype "passive"))
    )
    (net (code "117") (name "Net-(U13-XTAL1)") (class "Default")
      (node (ref "C52") (pin "2") (pinfunction "2_2") (pintype "passive"))
      (node (ref "U13") (pin "22") (pinfunction "XTAL1_22") (pintype "passive"))
      (node (ref "Y3") (pin "2") (pinfunction "OSC2_2") (pintype "passive"))
    )
    (net (code "118") (name "Net-(U13-XTAL2)") (class "Default")
      (node (ref "C51") (pin "2") (pinfunction "2_2") (pintype "passive"))
      (node (ref "U13") (pin "23") (pinfunction "XTAL2_23") (pintype "passive"))
      (node (ref "Y3") (pin "1") (pinfunction "OSC1_1") (pintype "passive"))
    )
    (net (code "119") (name "Net-(U23-~{HOLD})") (class "Default")
      (node (ref "R96") (pin "2") (pinfunction "2_2") (pintype "passive"))
      (node (ref "U23") (pin "7") (pinfunction "~{HOLD}_7") (pintype "passive"))
    )
    (net (code "120") (name "Net-(U23-~{WP})") (class "Default")
      (node (ref "R95") (pin "1") (pinfunction "1_1") (pintype "passive"))
      (node (ref "U23") (pin "3") (pinfunction "~{WP}_3") (pintype "passive"))
    )
    (net (code "121") (name "Net-(U24-MCLK_IN)") (class "Default")
      (node (ref "C50") (pin "2") (pinfunction "2_2") (pintype "passive"))
      (node (ref "U24") (pin "2") (pinfunction "MCLK_IN_2") (pintype "passive"))
      (node (ref "Y4") (pin "1") (pinfunction "OSC1_1") (pintype "passive"))
    )
    (net (code "122") (name "Net-(U24-MCLK_OUT)") (class "Default")
      (node (ref "C53") (pin "2") (pinfunction "2_2") (pintype "passive"))
      (node (ref "U24") (pin "3") (pinfunction "MCLK_OUT_3") (pintype "passive"))
      (node (ref "Y4") (pin "2") (pinfunction "OSC2_2") (pintype "passive"))
    )
    (net (code "123") (name "Vbat") (class "Default")
      (node (ref "JP1") (pin "6") (pinfunction "6_6") (pintype "passive"))
      (node (ref "U13") (pin "19") (pinfunction "VBAT_19") (pintype "passive"))
    )
    (net (code "124") (name "Vref") (class "Default")
      (node (ref "U13") (pin "10") (pinfunction "Vdda_10") (pintype "passive"))
      (node (ref "U13") (pin "12") (pinfunction "VREF_12") (pintype "passive"))
      (node (ref "U24") (pin "9") (pinfunction "REF_IN(+)_9") (pintype "passive"))
      (node (ref "U5") (pin "5") (pinfunction "OUT_5") (pintype "power_in"))
    )
    (net (code "125") (name "unconnected-(JP1-Pad4)") (class "Default")
      (node (ref "JP1") (pin "4") (pinfunction "4_4") (pintype "passive"))
    )
    (net (code "126") (name "unconnected-(JP4-Pad30)") (class "Default")
      (node (ref "JP4") (pin "30") (pinfunction "30_30") (pintype "passive"))
    )
    (net (code "127") (name "unconnected-(JP6-Pad10)") (class "Default")
      (node (ref "JP6") (pin "10") (pinfunction "10_10") (pintype "passive"))
    )
    (net (code "128") (name "unconnected-(JP11-Pad7)") (class "Default")
      (node (ref "JP11") (pin "7") (pinfunction "7_7") (pintype "passive"))
    )
    (net (code "129") (name "unconnected-(JP11-Pad8)") (class "Default")
      (node (ref "JP11") (pin "8") (pinfunction "8_8") (pintype "passive"))
    )
    (net (code "130") (name "unconnected-(U5-NC-Pad4)") (class "Default")
      (node (ref "U5") (pin "4") (pinfunction "NC_4") (pintype "passive"))
    )
    (net (code "131") (name "unconnected-(U11-Vref-Pad5)") (class "Default")
      (node (ref "U11") (pin "5") (pinfunction "Vref_5") (pintype "passive"))
    )
    (net (code "132") (name "unconnected-(U13-RTCK-Pad100)") (class "Default")
      (node (ref "U13") (pin "100") (pinfunction "RTCK_100") (pintype "passive"))
    )
    (net (code "133") (name "unconnected-(U13-TCK-Pad5)") (class "Default")
      (node (ref "U13") (pin "5") (pinfunction "TCK_5") (pintype "passive"))
    )
    (net (code "134") (name "unconnected-(U13-TDI-Pad2)") (class "Default")
      (node (ref "U13") (pin "2") (pinfunction "TDI_2") (pintype "passive"))
    )
    (net (code "135") (name "unconnected-(U13-TDO-Pad1)") (class "Default")
      (node (ref "U13") (pin "1") (pinfunction "TDO_1") (pintype "passive"))
    )
    (net (code "136") (name "unconnected-(U13-TMS-Pad3)") (class "Default")
      (node (ref "U13") (pin "3") (pinfunction "TMS_3") (pintype "passive"))
    )
    (net (code "137") (name "unconnected-(U13-~{RSTOUT}-Pad14)") (class "Default")
      (node (ref "U13") (pin "14") (pinfunction "~{RSTOUT}_14") (pintype "passive"))
    )
    (net (code "138") (name "unconnected-(U13-~{TRST}-Pad4)") (class "Default")
      (node (ref "U13") (pin "4") (pinfunction "~{TRST}_4") (pintype "passive"))
    )
    (net (code "139") (name "unconnected-(U24-~{DRDY}-Pad12)") (class "Default")
      (node (ref "U24") (pin "12") (pinfunction "~{DRDY}_12") (pintype "passive"))
    )
  )
)
